# extio.net
KiCad netlist of a schematic drawn in EAGLE
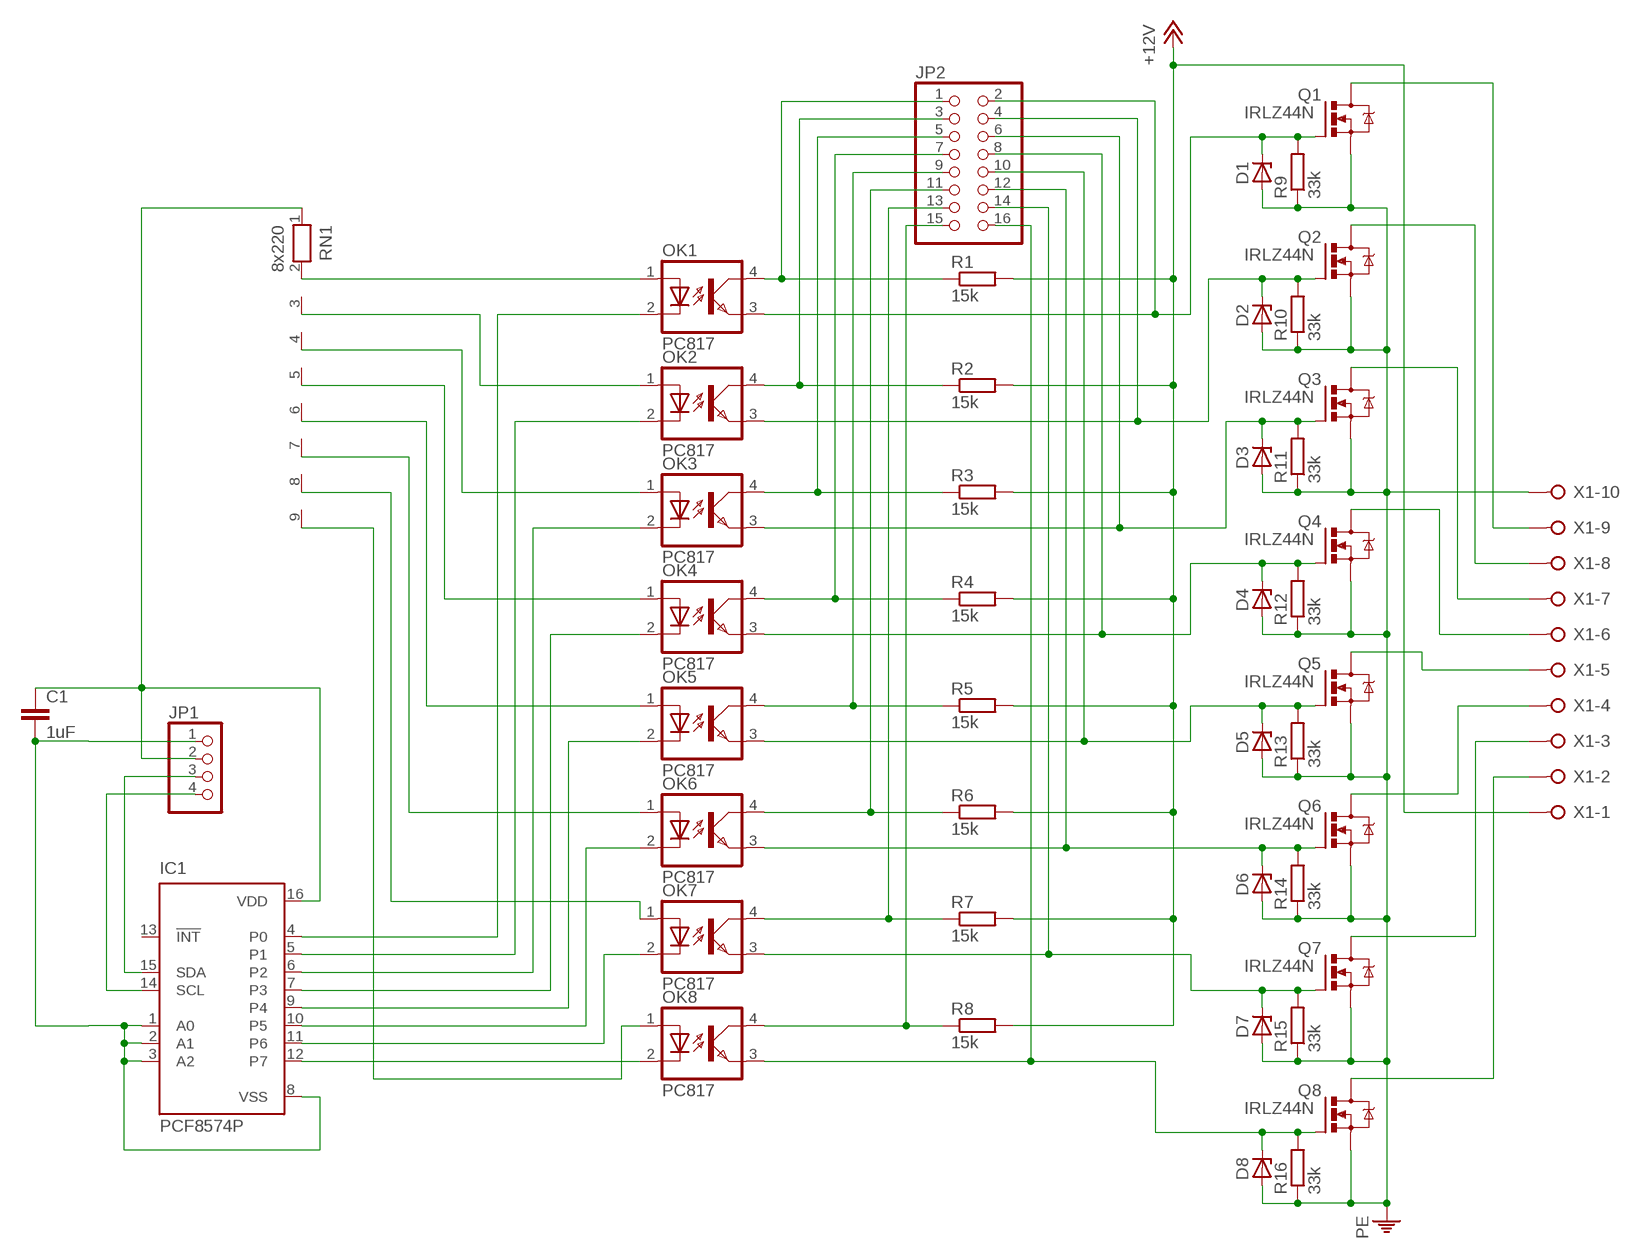
[diagram p0: schematic, sheet 1]

(export (version "E")
  (design (tool "Eeschema 10.0.6"))
  (components
    (comp (ref "C1")
      (value "1uF")
      (footprint "eagle-import:C0603")
      (libsource (lib "eagle-import") (part "C-EUC0603"))
    )
    (comp (ref "D1")
      (value "ZENER-DIODESOD80C")
      (footprint "eagle-import:SOD80C")
      (libsource (lib "eagle-import") (part "ZENER-DIODESOD80C"))
    )
    (comp (ref "D2")
      (value "ZENER-DIODESOD80C")
      (footprint "eagle-import:SOD80C")
      (libsource (lib "eagle-import") (part "ZENER-DIODESOD80C"))
    )
    (comp (ref "D3")
      (value "ZENER-DIODESOD80C")
      (footprint "eagle-import:SOD80C")
      (libsource (lib "eagle-import") (part "ZENER-DIODESOD80C"))
    )
    (comp (ref "D4")
      (value "ZENER-DIODESOD80C")
      (footprint "eagle-import:SOD80C")
      (libsource (lib "eagle-import") (part "ZENER-DIODESOD80C"))
    )
    (comp (ref "D5")
      (value "ZENER-DIODESOD80C")
      (footprint "eagle-import:SOD80C")
      (libsource (lib "eagle-import") (part "ZENER-DIODESOD80C"))
    )
    (comp (ref "D6")
      (value "ZENER-DIODESOD80C")
      (footprint "eagle-import:SOD80C")
      (libsource (lib "eagle-import") (part "ZENER-DIODESOD80C"))
    )
    (comp (ref "D7")
      (value "ZENER-DIODESOD80C")
      (footprint "eagle-import:SOD80C")
      (libsource (lib "eagle-import") (part "ZENER-DIODESOD80C"))
    )
    (comp (ref "D8")
      (value "ZENER-DIODESOD80C")
      (footprint "eagle-import:SOD80C")
      (libsource (lib "eagle-import") (part "ZENER-DIODESOD80C"))
    )
    (comp (ref "IC1")
      (value "PCF8574P")
      (footprint "eagle-import:DIL16")
      (fields (field (name "MPN") "PCF8574PN"))
      (libsource (lib "eagle-import") (part "PCF8574P"))
    )
    (comp (ref "JP1")
      (value "PINHD-1X4")
      (footprint "eagle-import:1X04")
      (libsource (lib "eagle-import") (part "PINHD-1X4"))
    )
    (comp (ref "JP2")
      (value "PINHD-2X8")
      (footprint "eagle-import:2X08")
      (libsource (lib "eagle-import") (part "PINHD-2X8"))
    )
    (comp (ref "OK1")
      (value "PC817")
      (footprint "eagle-import:DIL04")
      (fields (field (name "MPN") "PC817X4J000F"))
      (libsource (lib "eagle-import") (part "PC817"))
    )
    (comp (ref "OK2")
      (value "PC817")
      (footprint "eagle-import:DIL04")
      (fields (field (name "MPN") "PC817X4J000F"))
      (libsource (lib "eagle-import") (part "PC817"))
    )
    (comp (ref "OK3")
      (value "PC817")
      (footprint "eagle-import:DIL04")
      (fields (field (name "MPN") "PC817X4J000F"))
      (libsource (lib "eagle-import") (part "PC817"))
    )
    (comp (ref "OK4")
      (value "PC817")
      (footprint "eagle-import:DIL04")
      (fields (field (name "MPN") "PC817X4J000F"))
      (libsource (lib "eagle-import") (part "PC817"))
    )
    (comp (ref "OK5")
      (value "PC817")
      (footprint "eagle-import:DIL04")
      (fields (field (name "MPN") "PC817X4J000F"))
      (libsource (lib "eagle-import") (part "PC817"))
    )
    (comp (ref "OK6")
      (value "PC817")
      (footprint "eagle-import:DIL04")
      (fields (field (name "MPN") "PC817X4J000F"))
      (libsource (lib "eagle-import") (part "PC817"))
    )
    (comp (ref "OK7")
      (value "PC817")
      (footprint "eagle-import:DIL04")
      (fields (field (name "MPN") "PC817X4J000F"))
      (libsource (lib "eagle-import") (part "PC817"))
    )
    (comp (ref "OK8")
      (value "PC817")
      (footprint "eagle-import:DIL04")
      (fields (field (name "MPN") "PC817X4J000F"))
      (libsource (lib "eagle-import") (part "PC817"))
    )
    (comp (ref "Q1")
      (value "IRLZ44N")
      (footprint "eagle-import:TO220V")
      (libsource (lib "eagle-import") (part "IRLZ44N"))
    )
    (comp (ref "Q2")
      (value "IRLZ44N")
      (footprint "eagle-import:TO220V")
      (libsource (lib "eagle-import") (part "IRLZ44N"))
    )
    (comp (ref "Q3")
      (value "IRLZ44N")
      (footprint "eagle-import:TO220V")
      (libsource (lib "eagle-import") (part "IRLZ44N"))
    )
    (comp (ref "Q4")
      (value "IRLZ44N")
      (footprint "eagle-import:TO220V")
      (libsource (lib "eagle-import") (part "IRLZ44N"))
    )
    (comp (ref "Q5")
      (value "IRLZ44N")
      (footprint "eagle-import:TO220V")
      (libsource (lib "eagle-import") (part "IRLZ44N"))
    )
    (comp (ref "Q6")
      (value "IRLZ44N")
      (footprint "eagle-import:TO220V")
      (libsource (lib "eagle-import") (part "IRLZ44N"))
    )
    (comp (ref "Q7")
      (value "IRLZ44N")
      (footprint "eagle-import:TO220V")
      (libsource (lib "eagle-import") (part "IRLZ44N"))
    )
    (comp (ref "Q8")
      (value "IRLZ44N")
      (footprint "eagle-import:TO220V")
      (libsource (lib "eagle-import") (part "IRLZ44N"))
    )
    (comp (ref "R1")
      (value "15k")
      (footprint "eagle-import:R0603")
      (libsource (lib "eagle-import") (part "R-EU_R0603"))
    )
    (comp (ref "R2")
      (value "15k")
      (footprint "eagle-import:R0603")
      (libsource (lib "eagle-import") (part "R-EU_R0603"))
    )
    (comp (ref "R3")
      (value "15k")
      (footprint "eagle-import:R0603")
      (libsource (lib "eagle-import") (part "R-EU_R0603"))
    )
    (comp (ref "R4")
      (value "15k")
      (footprint "eagle-import:R0603")
      (libsource (lib "eagle-import") (part "R-EU_R0603"))
    )
    (comp (ref "R5")
      (value "15k")
      (footprint "eagle-import:R0603")
      (libsource (lib "eagle-import") (part "R-EU_R0603"))
    )
    (comp (ref "R6")
      (value "15k")
      (footprint "eagle-import:R0603")
      (libsource (lib "eagle-import") (part "R-EU_R0603"))
    )
    (comp (ref "R7")
      (value "15k")
      (footprint "eagle-import:R0603")
      (libsource (lib "eagle-import") (part "R-EU_R0603"))
    )
    (comp (ref "R8")
      (value "15k")
      (footprint "eagle-import:R0603")
      (libsource (lib "eagle-import") (part "R-EU_R0603"))
    )
    (comp (ref "R9")
      (value "33k")
      (footprint "eagle-import:R0603")
      (libsource (lib "eagle-import") (part "R-EU_R0603"))
    )
    (comp (ref "R10")
      (value "33k")
      (footprint "eagle-import:R0603")
      (libsource (lib "eagle-import") (part "R-EU_R0603"))
    )
    (comp (ref "R11")
      (value "33k")
      (footprint "eagle-import:R0603")
      (libsource (lib "eagle-import") (part "R-EU_R0603"))
    )
    (comp (ref "R12")
      (value "33k")
      (footprint "eagle-import:R0603")
      (libsource (lib "eagle-import") (part "R-EU_R0603"))
    )
    (comp (ref "R13")
      (value "33k")
      (footprint "eagle-import:R0603")
      (libsource (lib "eagle-import") (part "R-EU_R0603"))
    )
    (comp (ref "R14")
      (value "33k")
      (footprint "eagle-import:R0603")
      (libsource (lib "eagle-import") (part "R-EU_R0603"))
    )
    (comp (ref "R15")
      (value "33k")
      (footprint "eagle-import:R0603")
      (libsource (lib "eagle-import") (part "R-EU_R0603"))
    )
    (comp (ref "R16")
      (value "33k")
      (footprint "eagle-import:R0603")
      (libsource (lib "eagle-import") (part "R-EU_R0603"))
    )
    (comp (ref "RN1")
      (value "8x220")
      (footprint "eagle-import:RN-9")
      (libsource (lib "eagle-import") (part "RN08"))
    )
    (comp (ref "X1")
      (value "W237-10P")
      (footprint "eagle-import:W237-10P")
      (libsource (lib "eagle-import") (part "W237-10P"))
    )
  )
  (nets
    (net (code "1") (name "+12V") (class "Default")
      (node (ref "R1") (pin "2") (pinfunction "2_2") (pintype "passive"))
      (node (ref "R2") (pin "2") (pinfunction "2_2") (pintype "passive"))
      (node (ref "R3") (pin "2") (pinfunction "2_2") (pintype "passive"))
      (node (ref "R4") (pin "2") (pinfunction "2_2") (pintype "passive"))
      (node (ref "R5") (pin "2") (pinfunction "2_2") (pintype "passive"))
      (node (ref "R6") (pin "2") (pinfunction "2_2") (pintype "passive"))
      (node (ref "R7") (pin "2") (pinfunction "2_2") (pintype "passive"))
      (node (ref "R8") (pin "2") (pinfunction "2_2") (pintype "passive"))
      (node (ref "X1") (pin "1") (pinfunction "KL_1") (pintype "passive"))
    )
    (net (code "2") (name "Net-(IC1-A0)") (class "Default")
      (node (ref "C1") (pin "2") (pinfunction "2_2") (pintype "passive"))
      (node (ref "IC1") (pin "1") (pinfunction "A0_1") (pintype "input"))
      (node (ref "IC1") (pin "2") (pinfunction "A1_2") (pintype "input"))
      (node (ref "IC1") (pin "3") (pinfunction "A2_3") (pintype "input"))
      (node (ref "IC1") (pin "8") (pinfunction "VSS_8") (pintype "power_in"))
      (node (ref "JP1") (pin "1") (pinfunction "1_1") (pintype "passive"))
    )
    (net (code "3") (name "Net-(IC1-P0)") (class "Default")
      (node (ref "IC1") (pin "4") (pinfunction "P0_4") (pintype "bidirectional"))
      (node (ref "OK1") (pin "2") (pinfunction "C_2") (pintype "passive"))
    )
    (net (code "4") (name "Net-(IC1-P1)") (class "Default")
      (node (ref "IC1") (pin "5") (pinfunction "P1_5") (pintype "bidirectional"))
      (node (ref "OK2") (pin "2") (pinfunction "C_2") (pintype "passive"))
    )
    (net (code "5") (name "Net-(IC1-P2)") (class "Default")
      (node (ref "IC1") (pin "6") (pinfunction "P2_6") (pintype "bidirectional"))
      (node (ref "OK3") (pin "2") (pinfunction "C_2") (pintype "passive"))
    )
    (net (code "6") (name "Net-(IC1-P3)") (class "Default")
      (node (ref "IC1") (pin "7") (pinfunction "P3_7") (pintype "bidirectional"))
      (node (ref "OK4") (pin "2") (pinfunction "C_2") (pintype "passive"))
    )
    (net (code "7") (name "Net-(IC1-P4)") (class "Default")
      (node (ref "IC1") (pin "9") (pinfunction "P4_9") (pintype "bidirectional"))
      (node (ref "OK5") (pin "2") (pinfunction "C_2") (pintype "passive"))
    )
    (net (code "8") (name "Net-(IC1-P5)") (class "Default")
      (node (ref "IC1") (pin "10") (pinfunction "P5_10") (pintype "bidirectional"))
      (node (ref "OK6") (pin "2") (pinfunction "C_2") (pintype "passive"))
    )
    (net (code "9") (name "Net-(IC1-P6)") (class "Default")
      (node (ref "IC1") (pin "11") (pinfunction "P6_11") (pintype "bidirectional"))
      (node (ref "OK7") (pin "2") (pinfunction "C_2") (pintype "passive"))
    )
    (net (code "10") (name "Net-(IC1-P7)") (class "Default")
      (node (ref "IC1") (pin "12") (pinfunction "P7_12") (pintype "bidirectional"))
      (node (ref "OK8") (pin "2") (pinfunction "C_2") (pintype "passive"))
    )
    (net (code "11") (name "Net-(IC1-SCL)") (class "Default")
      (node (ref "IC1") (pin "14") (pinfunction "SCL_14") (pintype "input"))
      (node (ref "JP1") (pin "4") (pinfunction "4_4") (pintype "passive"))
    )
    (net (code "12") (name "Net-(IC1-SDA)") (class "Default")
      (node (ref "IC1") (pin "15") (pinfunction "SDA_15") (pintype "bidirectional"))
      (node (ref "JP1") (pin "3") (pinfunction "3_3") (pintype "passive"))
    )
    (net (code "13") (name "Net-(IC1-VDD)") (class "Default")
      (node (ref "C1") (pin "1") (pinfunction "1_1") (pintype "passive"))
      (node (ref "IC1") (pin "16") (pinfunction "VDD_16") (pintype "power_in"))
      (node (ref "JP1") (pin "2") (pinfunction "2_2") (pintype "passive"))
      (node (ref "RN1") (pin "1") (pinfunction "1_1") (pintype "passive"))
    )
    (net (code "14") (name "Net-(OK1-A)") (class "Default")
      (node (ref "OK1") (pin "1") (pinfunction "A_1") (pintype "passive"))
      (node (ref "RN1") (pin "2") (pinfunction "2_2") (pintype "passive"))
    )
    (net (code "15") (name "Net-(OK1-COL)") (class "Default")
      (node (ref "JP2") (pin "1") (pinfunction "1_1") (pintype "passive"))
      (node (ref "OK1") (pin "4") (pinfunction "COL_4") (pintype "passive"))
      (node (ref "R1") (pin "1") (pinfunction "1_1") (pintype "passive"))
    )
    (net (code "16") (name "Net-(OK1-EMIT)") (class "Default")
      (node (ref "D1") (pin "C") (pinfunction "C_C") (pintype "passive"))
      (node (ref "JP2") (pin "2") (pinfunction "2_2") (pintype "passive"))
      (node (ref "OK1") (pin "3") (pinfunction "EMIT_3") (pintype "passive"))
      (node (ref "Q1") (pin "1") (pinfunction "G_1") (pintype "passive"))
      (node (ref "R9") (pin "2") (pinfunction "2_2") (pintype "passive"))
    )
    (net (code "17") (name "Net-(OK2-A)") (class "Default")
      (node (ref "OK2") (pin "1") (pinfunction "A_1") (pintype "passive"))
      (node (ref "RN1") (pin "3") (pinfunction "3_3") (pintype "passive"))
    )
    (net (code "18") (name "Net-(OK2-COL)") (class "Default")
      (node (ref "JP2") (pin "3") (pinfunction "3_3") (pintype "passive"))
      (node (ref "OK2") (pin "4") (pinfunction "COL_4") (pintype "passive"))
      (node (ref "R2") (pin "1") (pinfunction "1_1") (pintype "passive"))
    )
    (net (code "19") (name "Net-(OK2-EMIT)") (class "Default")
      (node (ref "D2") (pin "C") (pinfunction "C_C") (pintype "passive"))
      (node (ref "JP2") (pin "4") (pinfunction "4_4") (pintype "passive"))
      (node (ref "OK2") (pin "3") (pinfunction "EMIT_3") (pintype "passive"))
      (node (ref "Q2") (pin "1") (pinfunction "G_1") (pintype "passive"))
      (node (ref "R10") (pin "2") (pinfunction "2_2") (pintype "passive"))
    )
    (net (code "20") (name "Net-(OK3-A)") (class "Default")
      (node (ref "OK3") (pin "1") (pinfunction "A_1") (pintype "passive"))
      (node (ref "RN1") (pin "4") (pinfunction "4_4") (pintype "passive"))
    )
    (net (code "21") (name "Net-(OK3-COL)") (class "Default")
      (node (ref "JP2") (pin "5") (pinfunction "5_5") (pintype "passive"))
      (node (ref "OK3") (pin "4") (pinfunction "COL_4") (pintype "passive"))
      (node (ref "R3") (pin "1") (pinfunction "1_1") (pintype "passive"))
    )
    (net (code "22") (name "Net-(OK3-EMIT)") (class "Default")
      (node (ref "D3") (pin "C") (pinfunction "C_C") (pintype "passive"))
      (node (ref "JP2") (pin "6") (pinfunction "6_6") (pintype "passive"))
      (node (ref "OK3") (pin "3") (pinfunction "EMIT_3") (pintype "passive"))
      (node (ref "Q3") (pin "1") (pinfunction "G_1") (pintype "passive"))
      (node (ref "R11") (pin "2") (pinfunction "2_2") (pintype "passive"))
    )
    (net (code "23") (name "Net-(OK4-A)") (class "Default")
      (node (ref "OK4") (pin "1") (pinfunction "A_1") (pintype "passive"))
      (node (ref "RN1") (pin "5") (pinfunction "5_5") (pintype "passive"))
    )
    (net (code "24") (name "Net-(OK4-COL)") (class "Default")
      (node (ref "JP2") (pin "7") (pinfunction "7_7") (pintype "passive"))
      (node (ref "OK4") (pin "4") (pinfunction "COL_4") (pintype "passive"))
      (node (ref "R4") (pin "1") (pinfunction "1_1") (pintype "passive"))
    )
    (net (code "25") (name "Net-(OK4-EMIT)") (class "Default")
      (node (ref "D4") (pin "C") (pinfunction "C_C") (pintype "passive"))
      (node (ref "JP2") (pin "8") (pinfunction "8_8") (pintype "passive"))
      (node (ref "OK4") (pin "3") (pinfunction "EMIT_3") (pintype "passive"))
      (node (ref "Q4") (pin "1") (pinfunction "G_1") (pintype "passive"))
      (node (ref "R12") (pin "2") (pinfunction "2_2") (pintype "passive"))
    )
    (net (code "26") (name "Net-(OK5-A)") (class "Default")
      (node (ref "OK5") (pin "1") (pinfunction "A_1") (pintype "passive"))
      (node (ref "RN1") (pin "6") (pinfunction "6_6") (pintype "passive"))
    )
    (net (code "27") (name "Net-(OK5-COL)") (class "Default")
      (node (ref "JP2") (pin "9") (pinfunction "9_9") (pintype "passive"))
      (node (ref "OK5") (pin "4") (pinfunction "COL_4") (pintype "passive"))
      (node (ref "R5") (pin "1") (pinfunction "1_1") (pintype "passive"))
    )
    (net (code "28") (name "Net-(OK5-EMIT)") (class "Default")
      (node (ref "D5") (pin "C") (pinfunction "C_C") (pintype "passive"))
      (node (ref "JP2") (pin "10") (pinfunction "10_10") (pintype "passive"))
      (node (ref "OK5") (pin "3") (pinfunction "EMIT_3") (pintype "passive"))
      (node (ref "Q5") (pin "1") (pinfunction "G_1") (pintype "passive"))
      (node (ref "R13") (pin "2") (pinfunction "2_2") (pintype "passive"))
    )
    (net (code "29") (name "Net-(OK6-A)") (class "Default")
      (node (ref "OK6") (pin "1") (pinfunction "A_1") (pintype "passive"))
      (node (ref "RN1") (pin "7") (pinfunction "7_7") (pintype "passive"))
    )
    (net (code "30") (name "Net-(OK6-COL)") (class "Default")
      (node (ref "JP2") (pin "11") (pinfunction "11_11") (pintype "passive"))
      (node (ref "OK6") (pin "4") (pinfunction "COL_4") (pintype "passive"))
      (node (ref "R6") (pin "1") (pinfunction "1_1") (pintype "passive"))
    )
    (net (code "31") (name "Net-(OK6-EMIT)") (class "Default")
      (node (ref "D6") (pin "C") (pinfunction "C_C") (pintype "passive"))
      (node (ref "JP2") (pin "12") (pinfunction "12_12") (pintype "passive"))
      (node (ref "OK6") (pin "3") (pinfunction "EMIT_3") (pintype "passive"))
      (node (ref "Q6") (pin "1") (pinfunction "G_1") (pintype "passive"))
      (node (ref "R14") (pin "2") (pinfunction "2_2") (pintype "passive"))
    )
    (net (code "32") (name "Net-(OK7-A)") (class "Default")
      (node (ref "OK7") (pin "1") (pinfunction "A_1") (pintype "passive"))
      (node (ref "RN1") (pin "8") (pinfunction "8_8") (pintype "passive"))
    )
    (net (code "33") (name "Net-(OK7-COL)") (class "Default")
      (node (ref "JP2") (pin "13") (pinfunction "13_13") (pintype "passive"))
      (node (ref "OK7") (pin "4") (pinfunction "COL_4") (pintype "passive"))
      (node (ref "R7") (pin "1") (pinfunction "1_1") (pintype "passive"))
    )
    (net (code "34") (name "Net-(OK7-EMIT)") (class "Default")
      (node (ref "D7") (pin "C") (pinfunction "C_C") (pintype "passive"))
      (node (ref "JP2") (pin "14") (pinfunction "14_14") (pintype "passive"))
      (node (ref "OK7") (pin "3") (pinfunction "EMIT_3") (pintype "passive"))
      (node (ref "Q7") (pin "1") (pinfunction "G_1") (pintype "passive"))
      (node (ref "R15") (pin "2") (pinfunction "2_2") (pintype "passive"))
    )
    (net (code "35") (name "Net-(OK8-A)") (class "Default")
      (node (ref "OK8") (pin "1") (pinfunction "A_1") (pintype "passive"))
      (node (ref "RN1") (pin "9") (pinfunction "9_9") (pintype "passive"))
    )
    (net (code "36") (name "Net-(OK8-COL)") (class "Default")
      (node (ref "JP2") (pin "15") (pinfunction "15_15") (pintype "passive"))
      (node (ref "OK8") (pin "4") (pinfunction "COL_4") (pintype "passive"))
      (node (ref "R8") (pin "1") (pinfunction "1_1") (pintype "passive"))
    )
    (net (code "37") (name "Net-(OK8-EMIT)") (class "Default")
      (node (ref "D8") (pin "C") (pinfunction "C_C") (pintype "passive"))
      (node (ref "JP2") (pin "16") (pinfunction "16_16") (pintype "passive"))
      (node (ref "OK8") (pin "3") (pinfunction "EMIT_3") (pintype "passive"))
      (node (ref "Q8") (pin "1") (pinfunction "G_1") (pintype "passive"))
      (node (ref "R16") (pin "2") (pinfunction "2_2") (pintype "passive"))
    )
    (net (code "38") (name "Net-(Q1-D)") (class "Default")
      (node (ref "Q1") (pin "2") (pinfunction "D_2") (pintype "passive"))
      (node (ref "X1") (pin "9") (pinfunction "KL_9") (pintype "passive"))
    )
    (net (code "39") (name "Net-(Q2-D)") (class "Default")
      (node (ref "Q2") (pin "2") (pinfunction "D_2") (pintype "passive"))
      (node (ref "X1") (pin "8") (pinfunction "KL_8") (pintype "passive"))
    )
    (net (code "40") (name "Net-(Q3-D)") (class "Default")
      (node (ref "Q3") (pin "2") (pinfunction "D_2") (pintype "passive"))
      (node (ref "X1") (pin "7") (pinfunction "KL_7") (pintype "passive"))
    )
    (net (code "41") (name "Net-(Q4-D)") (class "Default")
      (node (ref "Q4") (pin "2") (pinfunction "D_2") (pintype "passive"))
      (node (ref "X1") (pin "6") (pinfunction "KL_6") (pintype "passive"))
    )
    (net (code "42") (name "Net-(Q5-D)") (class "Default")
      (node (ref "Q5") (pin "2") (pinfunction "D_2") (pintype "passive"))
      (node (ref "X1") (pin "5") (pinfunction "KL_5") (pintype "passive"))
    )
    (net (code "43") (name "Net-(Q6-D)") (class "Default")
      (node (ref "Q6") (pin "2") (pinfunction "D_2") (pintype "passive"))
      (node (ref "X1") (pin "4") (pinfunction "KL_4") (pintype "passive"))
    )
    (net (code "44") (name "Net-(Q7-D)") (class "Default")
      (node (ref "Q7") (pin "2") (pinfunction "D_2") (pintype "passive"))
      (node (ref "X1") (pin "3") (pinfunction "KL_3") (pintype "passive"))
    )
    (net (code "45") (name "Net-(Q8-D)") (class "Default")
      (node (ref "Q8") (pin "2") (pinfunction "D_2") (pintype "passive"))
      (node (ref "X1") (pin "2") (pinfunction "KL_2") (pintype "passive"))
    )
    (net (code "46") (name "PE") (class "Default")
      (node (ref "D1") (pin "A") (pinfunction "A_A") (pintype "passive"))
      (node (ref "D2") (pin "A") (pinfunction "A_A") (pintype "passive"))
      (node (ref "D3") (pin "A") (pinfunction "A_A") (pintype "passive"))
      (node (ref "D4") (pin "A") (pinfunction "A_A") (pintype "passive"))
      (node (ref "D5") (pin "A") (pinfunction "A_A") (pintype "passive"))
      (node (ref "D6") (pin "A") (pinfunction "A_A") (pintype "passive"))
      (node (ref "D7") (pin "A") (pinfunction "A_A") (pintype "passive"))
      (node (ref "D8") (pin "A") (pinfunction "A_A") (pintype "passive"))
      (node (ref "Q1") (pin "3") (pinfunction "S_3") (pintype "passive"))
      (node (ref "Q2") (pin "3") (pinfunction "S_3") (pintype "passive"))
      (node (ref "Q3") (pin "3") (pinfunction "S_3") (pintype "passive"))
      (node (ref "Q4") (pin "3") (pinfunction "S_3") (pintype "passive"))
      (node (ref "Q5") (pin "3") (pinfunction "S_3") (pintype "passive"))
      (node (ref "Q6") (pin "3") (pinfunction "S_3") (pintype "passive"))
      (node (ref "Q7") (pin "3") (pinfunction "S_3") (pintype "passive"))
      (node (ref "Q8") (pin "3") (pinfunction "S_3") (pintype "passive"))
      (node (ref "R10") (pin "1") (pinfunction "1_1") (pintype "passive"))
      (node (ref "R11") (pin "1") (pinfunction "1_1") (pintype "passive"))
      (node (ref "R12") (pin "1") (pinfunction "1_1") (pintype "passive"))
      (node (ref "R13") (pin "1") (pinfunction "1_1") (pintype "passive"))
      (node (ref "R14") (pin "1") (pinfunction "1_1") (pintype "passive"))
      (node (ref "R15") (pin "1") (pinfunction "1_1") (pintype "passive"))
      (node (ref "R16") (pin "1") (pinfunction "1_1") (pintype "passive"))
      (node (ref "R9") (pin "1") (pinfunction "1_1") (pintype "passive"))
      (node (ref "X1") (pin "10") (pinfunction "KL_10") (pintype "passive"))
    )
    (net (code "47") (name "unconnected-(IC1-~{INT}-Pad13)") (class "Default")
      (node (ref "IC1") (pin "13") (pinfunction "~{INT}_13") (pintype "output"))
    )
  )
)
